# SCH_fpga_v1_2023-12-09.net
KiCad netlist of a schematic drawn in EasyEDA
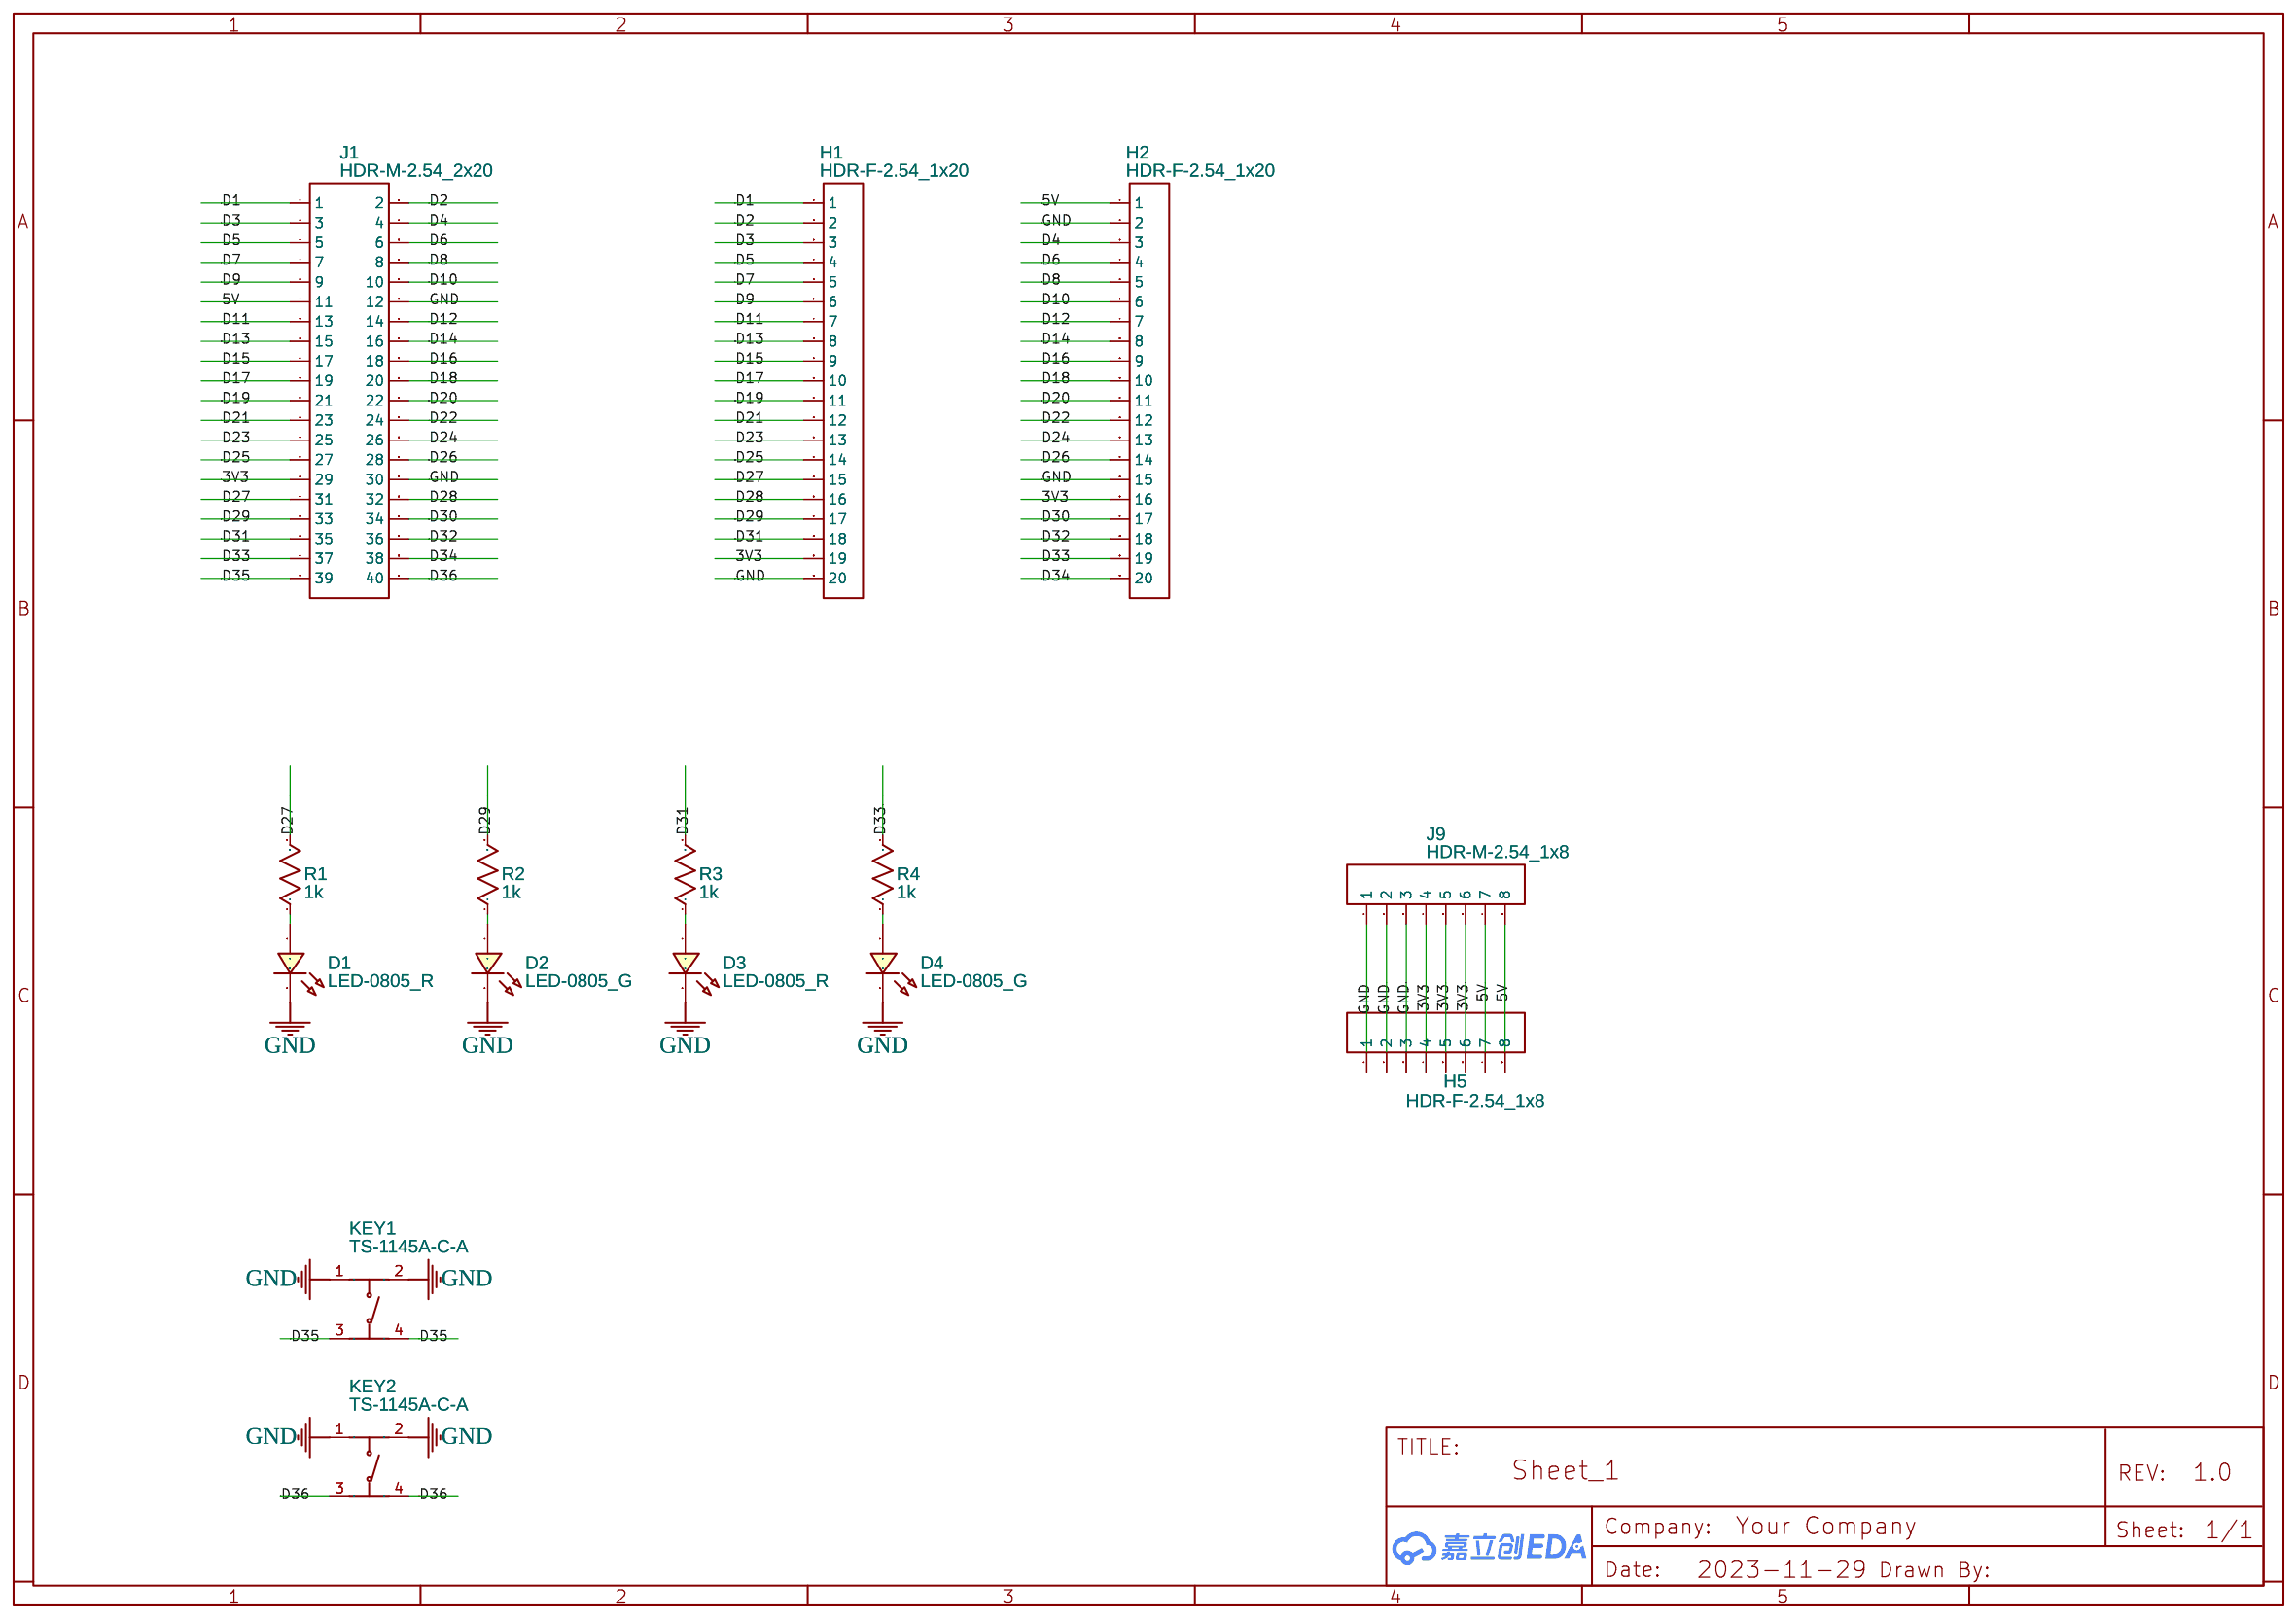
[diagram p0: Sheet_in]
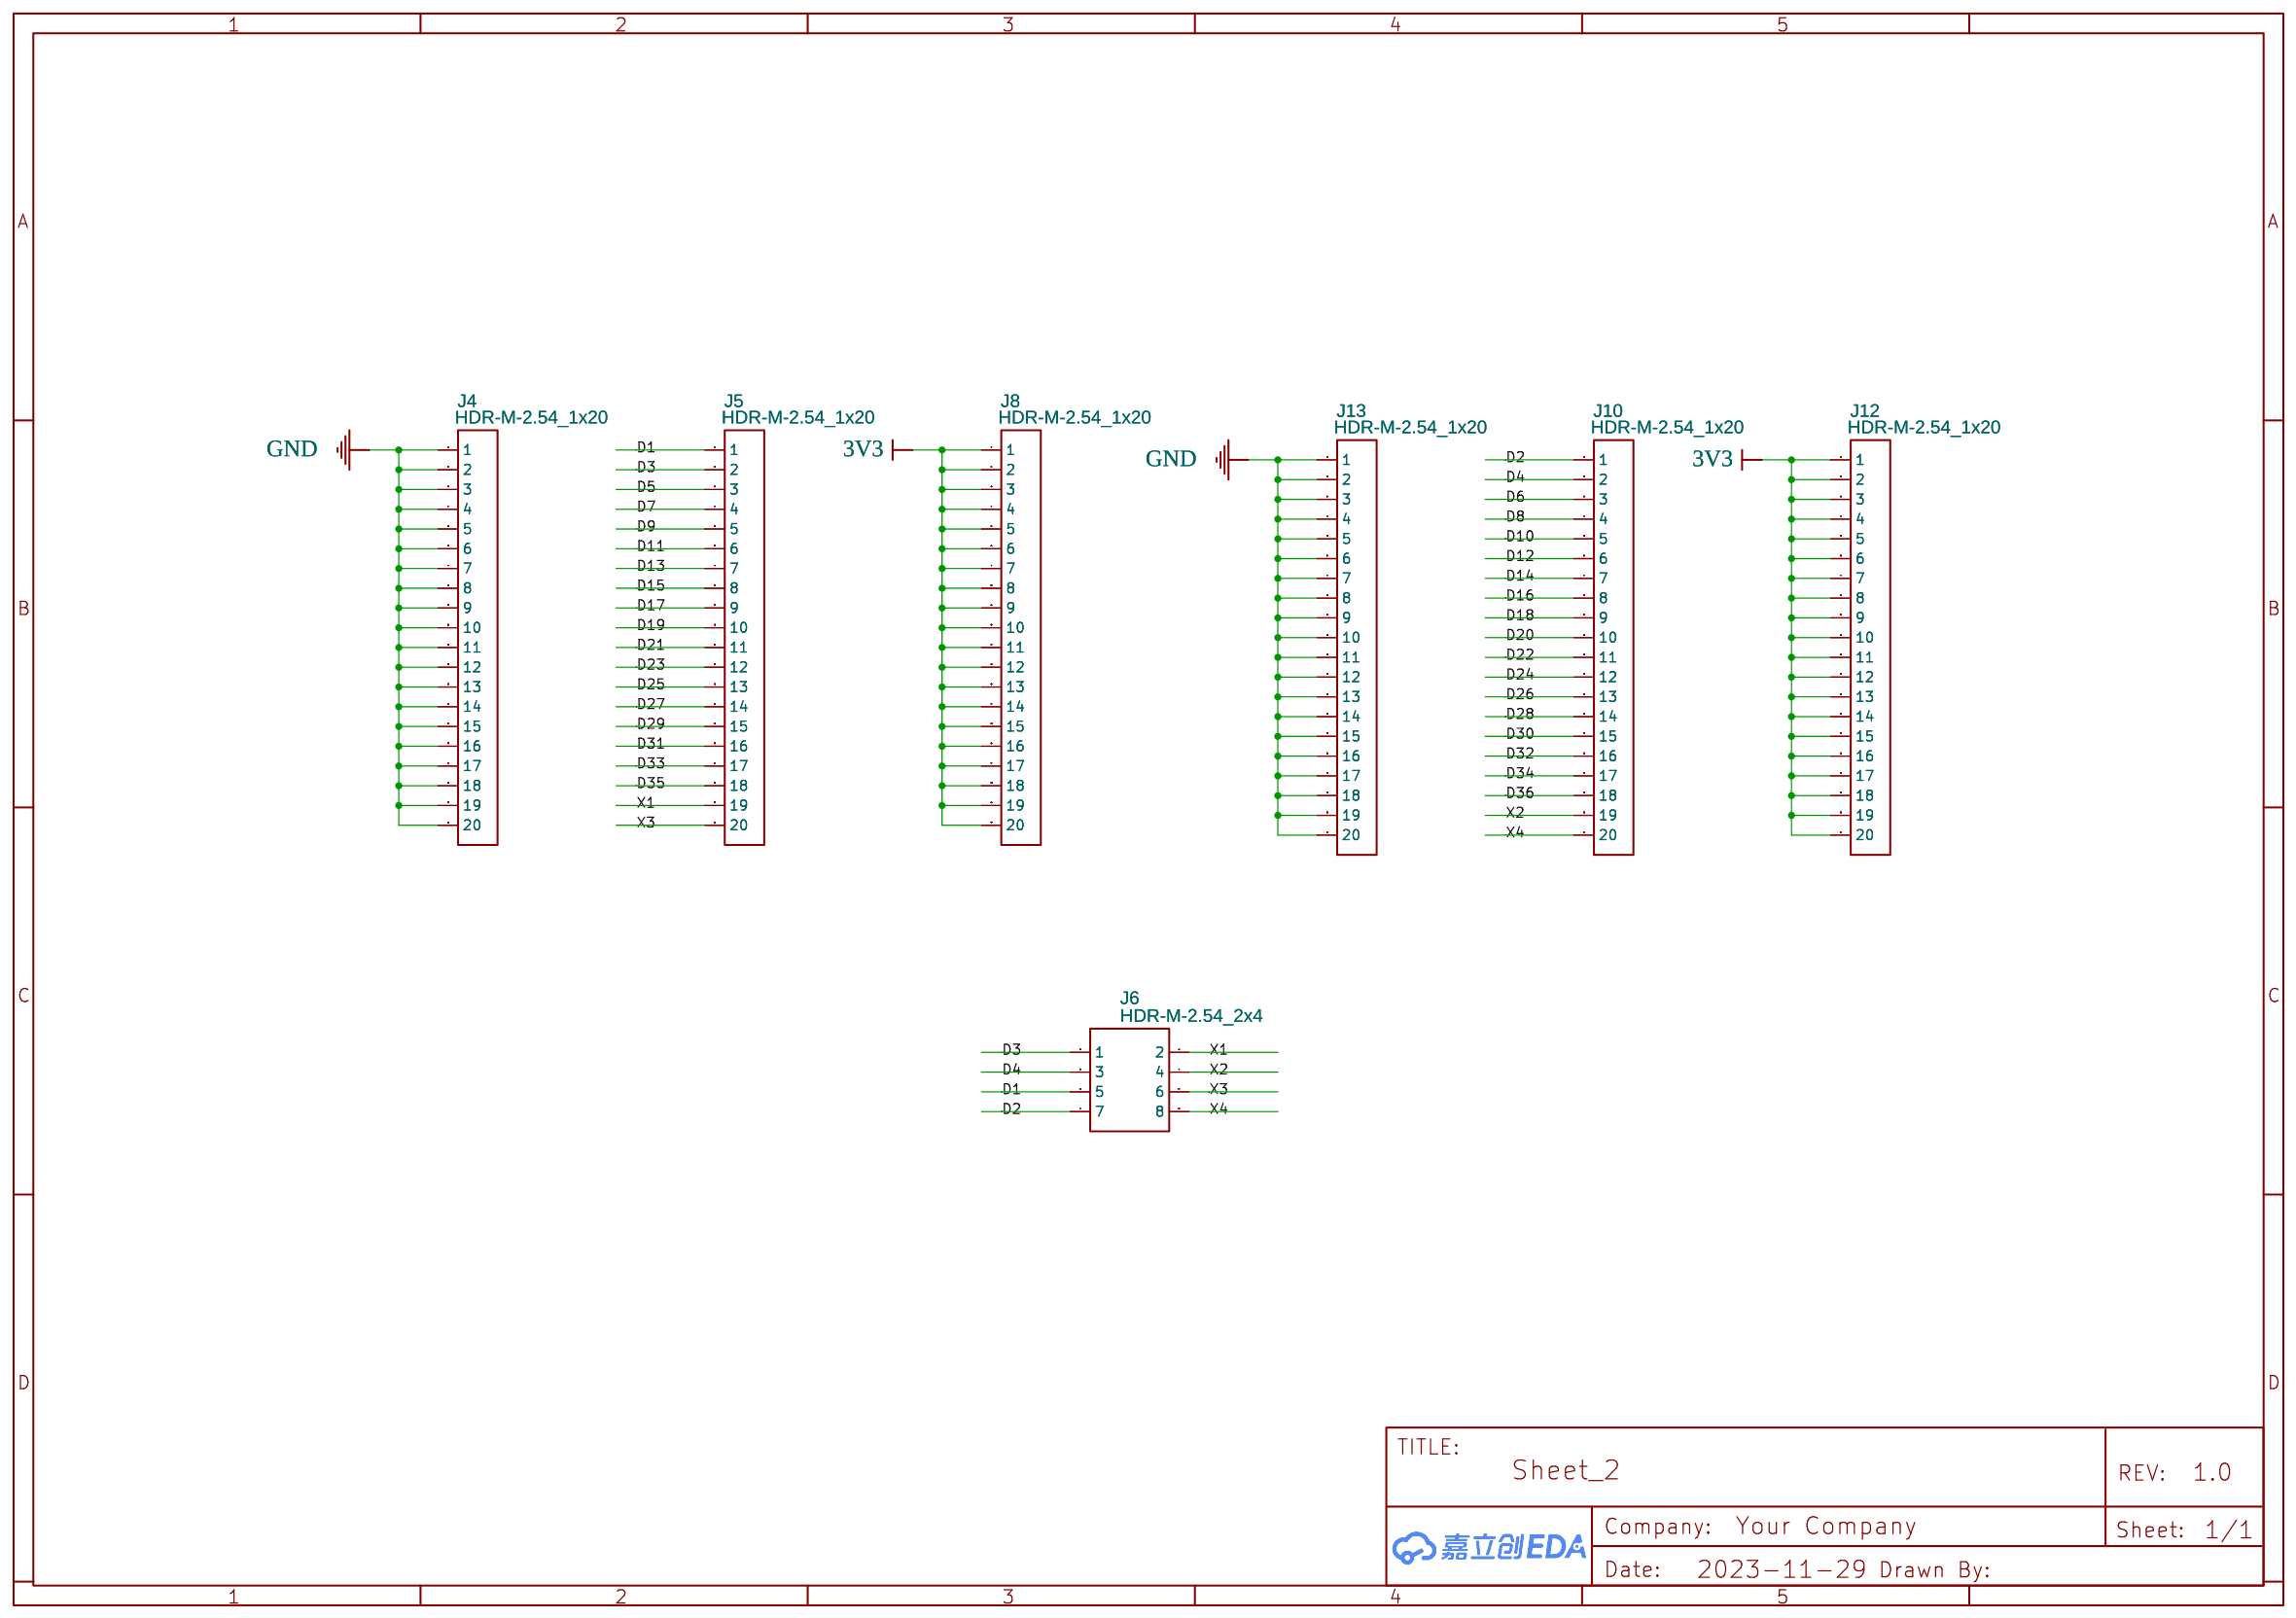
[diagram p1: Sheet_ctrl]
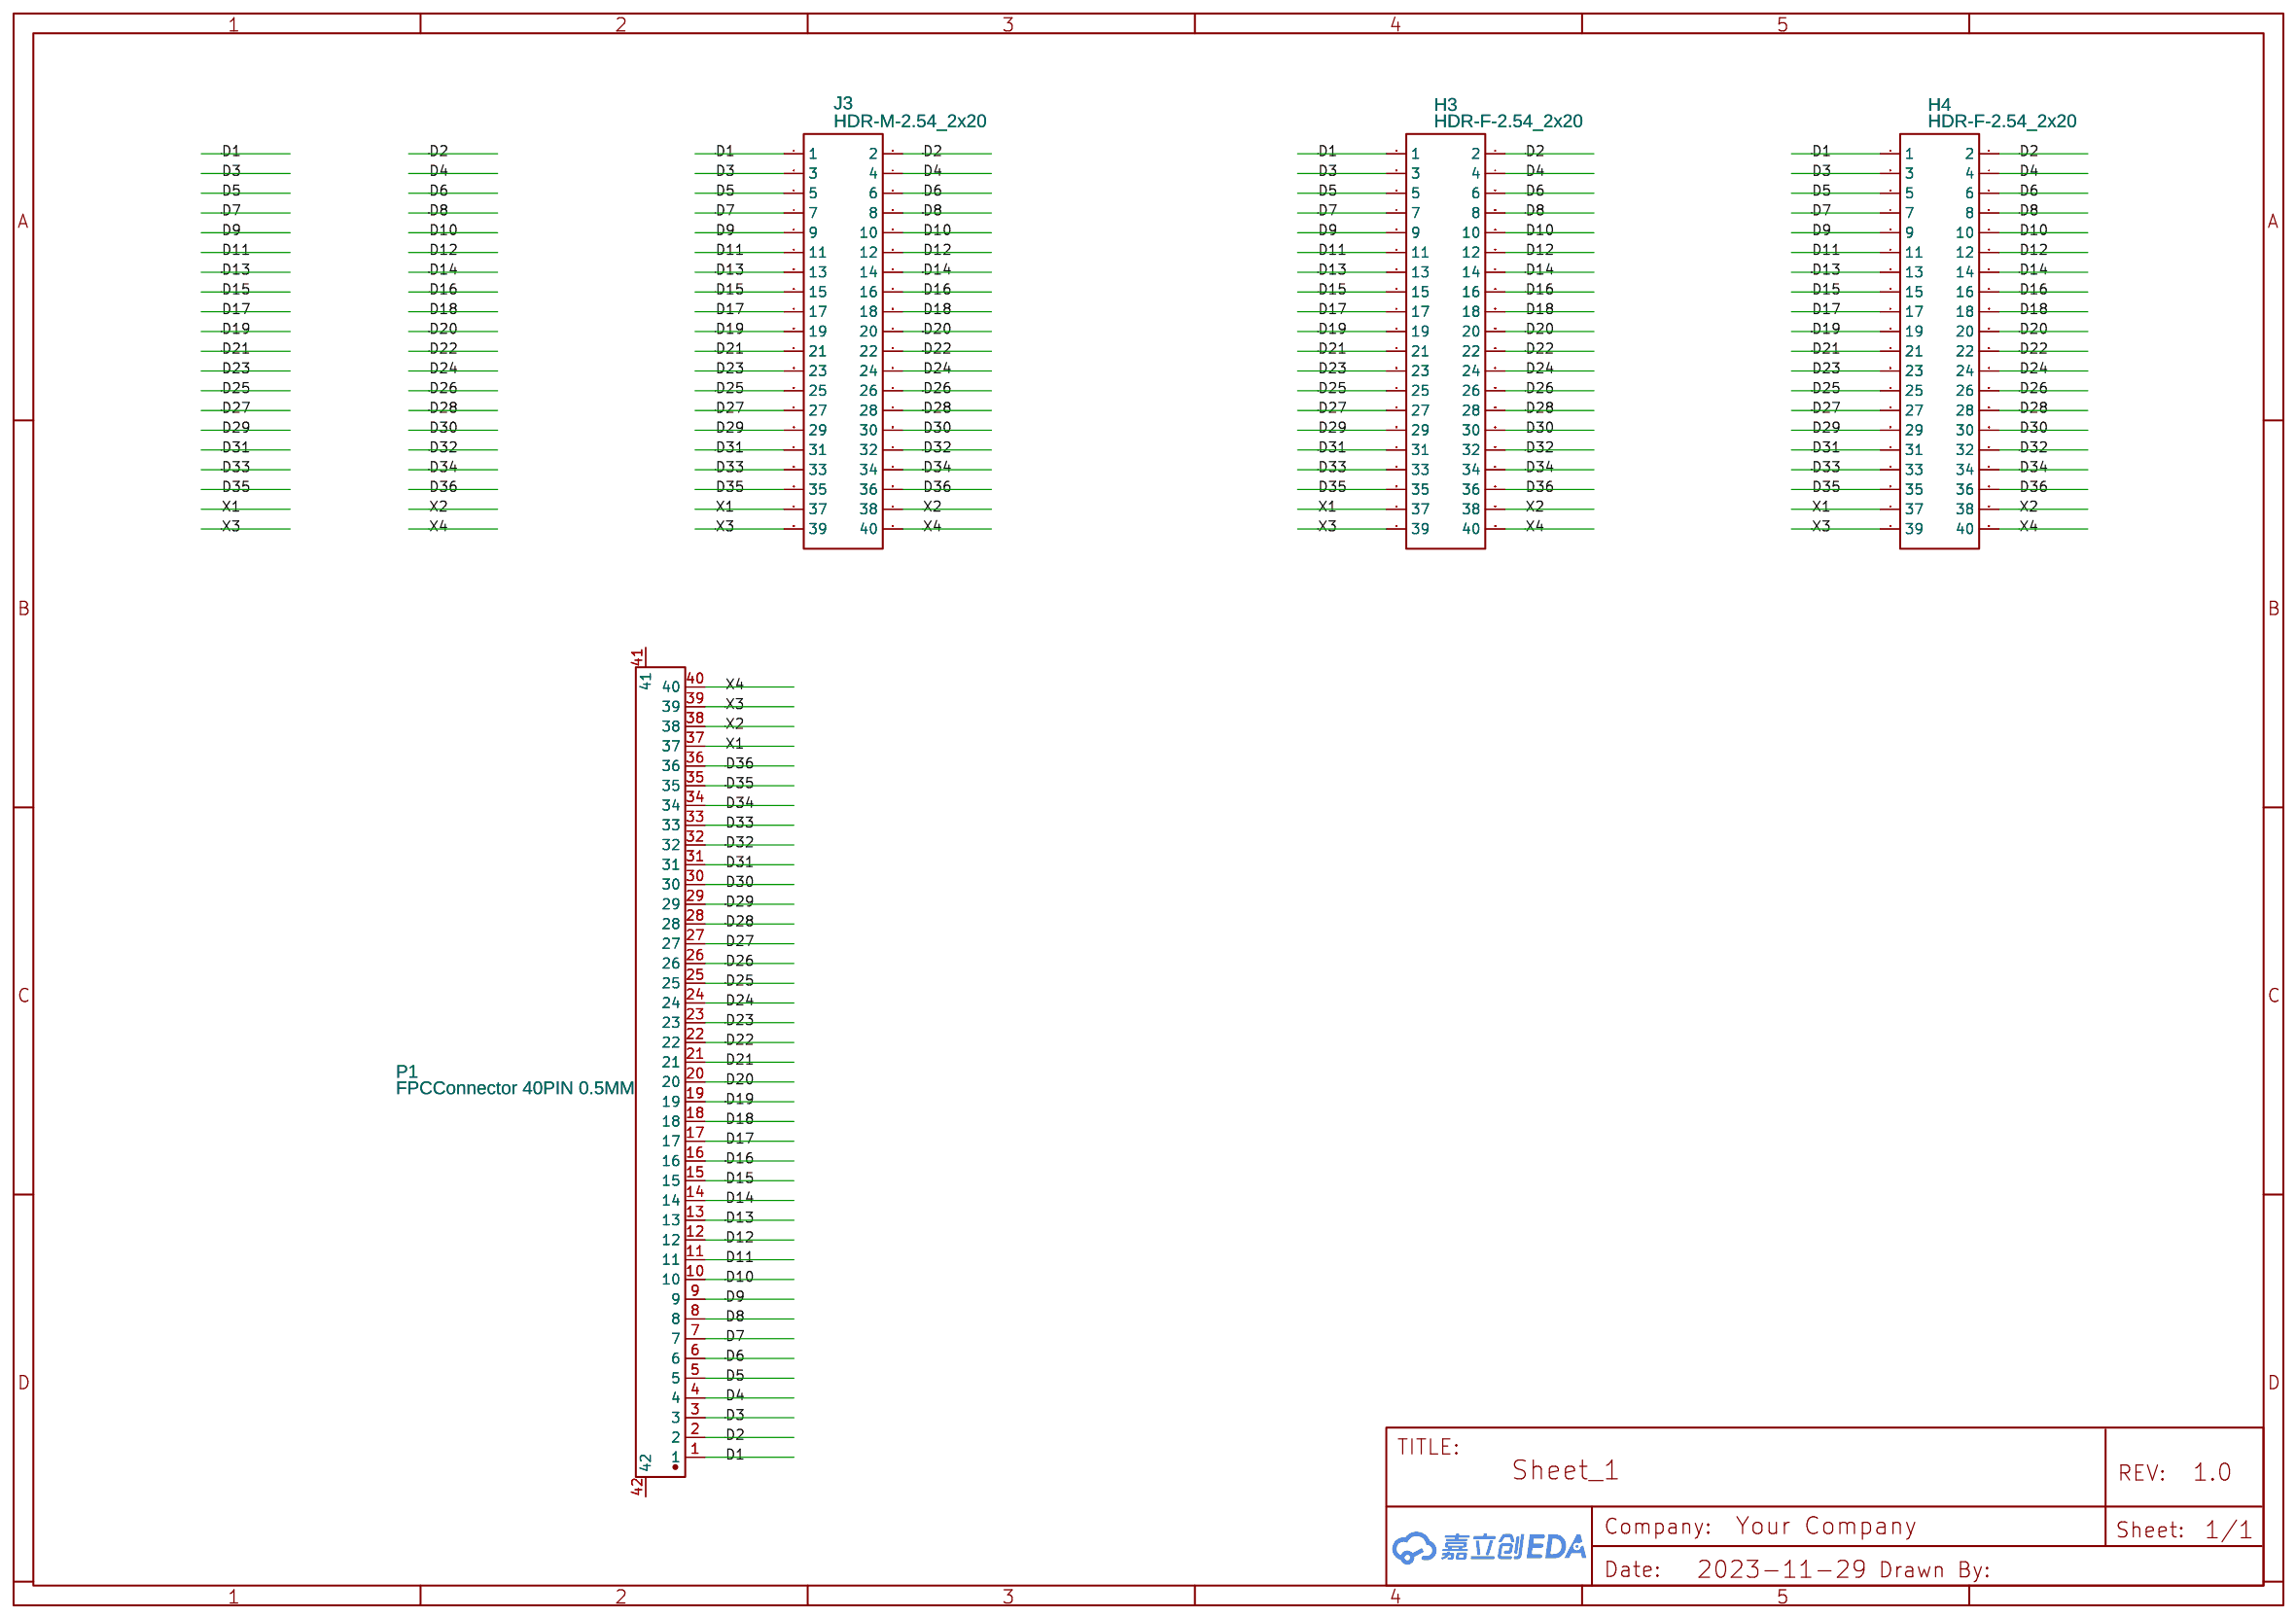
[diagram p2: Sheet_out]

(export (version "E")
  (design (tool "Eeschema 10.0.6"))
  (components
    (comp (ref "D1")
      (value "LED-0805_R")
      (fields
        (field (name "BOM_Manufacturer Part") "17-21SURC/S530-A3/TR8")
        (field (name "BOM_Supplier Part") "C72037")
      )
      (libsource (lib "") (part "LED-0805_R"))
    )
    (comp (ref "D2")
      (value "LED-0805_G")
      (fields (field (name "BOM_Manufacturer Part") "NCD0805G1") (field (name "BOM_Supplier Part") "C84260"))
      (libsource (lib "") (part "LED-0805_G"))
    )
    (comp (ref "D3")
      (value "LED-0805_R")
      (fields
        (field (name "BOM_Manufacturer Part") "17-21SURC/S530-A3/TR8")
        (field (name "BOM_Supplier Part") "C72037")
      )
      (libsource (lib "") (part "LED-0805_R"))
    )
    (comp (ref "D4")
      (value "LED-0805_G")
      (fields (field (name "BOM_Manufacturer Part") "NCD0805G1") (field (name "BOM_Supplier Part") "C84260"))
      (libsource (lib "") (part "LED-0805_G"))
    )
    (comp (ref "H1")
      (value "HDR-F-2.54_1x20")
      (fields (field (name "BOM_Supplier Part") "C50984"))
      (libsource (lib "") (part "HDR-F-2.54_1x20"))
    )
    (comp (ref "H2")
      (value "HDR-F-2.54_1x20")
      (fields (field (name "BOM_Supplier Part") "C50984"))
      (libsource (lib "") (part "HDR-F-2.54_1x20"))
    )
    (comp (ref "H5")
      (value "HDR-F-2.54_1x8")
      (fields (field (name "BOM_Supplier Part") "C225505"))
      (libsource (lib "") (part "HDR-F-2.54_1x8"))
    )
    (comp (ref "J1")
      (value "HDR-M-2.54_2x20")
      (fields (field (name "BOM_Supplier Part") "C50980"))
      (libsource (lib "") (part "HDR-M-2.54_2x20"))
    )
    (comp (ref "J9")
      (value "HDR-M-2.54_1x8")
      (fields (field (name "BOM_Supplier Part") "C190820"))
      (libsource (lib "") (part "HDR-M-2.54_1x8"))
    )
    (comp (ref "KEY1")
      (value "TS-1145A-C-A")
      (fields (field (name "BOM_Supplier Part") "C318903"))
      (libsource (lib "") (part "TS-1145A-C-A"))
    )
    (comp (ref "KEY2")
      (value "TS-1145A-C-A")
      (fields (field (name "BOM_Supplier Part") "C318903"))
      (libsource (lib "") (part "TS-1145A-C-A"))
    )
    (comp (ref "R1")
      (value "1k")
      (fields
        (field (name "BOM_Manufacturer Part") "TC0525F1001T5E")
        (field (name "BOM_Supplier Part") "C75781")
      )
      (libsource (lib "") (part "R_0805_US"))
    )
    (comp (ref "R2")
      (value "1k")
      (fields
        (field (name "BOM_Manufacturer Part") "TC0525F1001T5E")
        (field (name "BOM_Supplier Part") "C75781")
      )
      (libsource (lib "") (part "R_0805_US"))
    )
    (comp (ref "R3")
      (value "1k")
      (fields
        (field (name "BOM_Manufacturer Part") "TC0525F1001T5E")
        (field (name "BOM_Supplier Part") "C75781")
      )
      (libsource (lib "") (part "R_0805_US"))
    )
    (comp (ref "R4")
      (value "1k")
      (fields
        (field (name "BOM_Manufacturer Part") "TC0525F1001T5E")
        (field (name "BOM_Supplier Part") "C75781")
      )
      (libsource (lib "") (part "R_0805_US"))
    )
    (comp (ref "J4")
      (value "HDR-M-2.54_1x20")
      (fields (field (name "BOM_Supplier Part") "C50981"))
      (libsource (lib "") (part "HDR-M-2.54_1x20"))
    )
    (comp (ref "J5")
      (value "HDR-M-2.54_1x20")
      (fields (field (name "BOM_Supplier Part") "C50981"))
      (libsource (lib "") (part "HDR-M-2.54_1x20"))
    )
    (comp (ref "J6")
      (value "HDR-M-2.54_2x4")
      (fields (field (name "BOM_Supplier Part") "C58363"))
      (libsource (lib "") (part "HDR-M-2.54_2x4"))
    )
    (comp (ref "J8")
      (value "HDR-M-2.54_1x20")
      (fields (field (name "BOM_Supplier Part") "C50981"))
      (libsource (lib "") (part "HDR-M-2.54_1x20"))
    )
    (comp (ref "J10")
      (value "HDR-M-2.54_1x20")
      (fields (field (name "BOM_Supplier Part") "C50981"))
      (libsource (lib "") (part "HDR-M-2.54_1x20"))
    )
    (comp (ref "J12")
      (value "HDR-M-2.54_1x20")
      (fields (field (name "BOM_Supplier Part") "C50981"))
      (libsource (lib "") (part "HDR-M-2.54_1x20"))
    )
    (comp (ref "J13")
      (value "HDR-M-2.54_1x20")
      (fields (field (name "BOM_Supplier Part") "C50981"))
      (libsource (lib "") (part "HDR-M-2.54_1x20"))
    )
    (comp (ref "H3")
      (value "HDR-F-2.54_2x20")
      (fields (field (name "BOM_Supplier Part") "C50982"))
      (libsource (lib "") (part "HDR-F-2.54_2x20"))
    )
    (comp (ref "H4")
      (value "HDR-F-2.54_2x20")
      (fields (field (name "BOM_Supplier Part") "C50982"))
      (libsource (lib "") (part "HDR-F-2.54_2x20"))
    )
    (comp (ref "J3")
      (value "HDR-M-2.54_2x20")
      (fields (field (name "BOM_Supplier Part") "C50980"))
      (libsource (lib "") (part "HDR-M-2.54_2x20"))
    )
    (comp (ref "P1")
      (value "FPCConnector 40PIN 0.5MM")
      (fields (field (name "BOM_Manufacturer Part") "0.5-40P翻盖") (field (name "BOM_Supplier Part") "C9160"))
      (libsource (lib "") (part "FPCConnector 40PIN 0.5MM"))
    )
  )
  (nets
    (net (code "1") (name "3V3") (class "Default")
      (node (ref "H1") (pin "19") (pinfunction "19_19") (pintype "unspecified"))
      (node (ref "H2") (pin "16") (pinfunction "16_16") (pintype "unspecified"))
      (node (ref "H5") (pin "4") (pinfunction "4_4") (pintype "unspecified"))
      (node (ref "H5") (pin "5") (pinfunction "5_5") (pintype "unspecified"))
      (node (ref "H5") (pin "6") (pinfunction "6_6") (pintype "unspecified"))
      (node (ref "J1") (pin "29") (pinfunction "29_29") (pintype "input"))
      (node (ref "J12") (pin "1") (pinfunction "1_1") (pintype "unspecified"))
      (node (ref "J12") (pin "10") (pinfunction "10_10") (pintype "unspecified"))
      (node (ref "J12") (pin "11") (pinfunction "11_11") (pintype "unspecified"))
      (node (ref "J12") (pin "12") (pinfunction "12_12") (pintype "unspecified"))
      (node (ref "J12") (pin "13") (pinfunction "13_13") (pintype "unspecified"))
      (node (ref "J12") (pin "14") (pinfunction "14_14") (pintype "unspecified"))
      (node (ref "J12") (pin "15") (pinfunction "15_15") (pintype "unspecified"))
      (node (ref "J12") (pin "16") (pinfunction "16_16") (pintype "unspecified"))
      (node (ref "J12") (pin "17") (pinfunction "17_17") (pintype "unspecified"))
      (node (ref "J12") (pin "18") (pinfunction "18_18") (pintype "unspecified"))
      (node (ref "J12") (pin "19") (pinfunction "19_19") (pintype "unspecified"))
      (node (ref "J12") (pin "2") (pinfunction "2_2") (pintype "unspecified"))
      (node (ref "J12") (pin "20") (pinfunction "20_20") (pintype "unspecified"))
      (node (ref "J12") (pin "3") (pinfunction "3_3") (pintype "unspecified"))
      (node (ref "J12") (pin "4") (pinfunction "4_4") (pintype "unspecified"))
      (node (ref "J12") (pin "5") (pinfunction "5_5") (pintype "unspecified"))
      (node (ref "J12") (pin "6") (pinfunction "6_6") (pintype "unspecified"))
      (node (ref "J12") (pin "7") (pinfunction "7_7") (pintype "unspecified"))
      (node (ref "J12") (pin "8") (pinfunction "8_8") (pintype "unspecified"))
      (node (ref "J12") (pin "9") (pinfunction "9_9") (pintype "unspecified"))
      (node (ref "J8") (pin "1") (pinfunction "1_1") (pintype "unspecified"))
      (node (ref "J8") (pin "10") (pinfunction "10_10") (pintype "unspecified"))
      (node (ref "J8") (pin "11") (pinfunction "11_11") (pintype "unspecified"))
      (node (ref "J8") (pin "12") (pinfunction "12_12") (pintype "unspecified"))
      (node (ref "J8") (pin "13") (pinfunction "13_13") (pintype "unspecified"))
      (node (ref "J8") (pin "14") (pinfunction "14_14") (pintype "unspecified"))
      (node (ref "J8") (pin "15") (pinfunction "15_15") (pintype "unspecified"))
      (node (ref "J8") (pin "16") (pinfunction "16_16") (pintype "unspecified"))
      (node (ref "J8") (pin "17") (pinfunction "17_17") (pintype "unspecified"))
      (node (ref "J8") (pin "18") (pinfunction "18_18") (pintype "unspecified"))
      (node (ref "J8") (pin "19") (pinfunction "19_19") (pintype "unspecified"))
      (node (ref "J8") (pin "2") (pinfunction "2_2") (pintype "unspecified"))
      (node (ref "J8") (pin "20") (pinfunction "20_20") (pintype "unspecified"))
      (node (ref "J8") (pin "3") (pinfunction "3_3") (pintype "unspecified"))
      (node (ref "J8") (pin "4") (pinfunction "4_4") (pintype "unspecified"))
      (node (ref "J8") (pin "5") (pinfunction "5_5") (pintype "unspecified"))
      (node (ref "J8") (pin "6") (pinfunction "6_6") (pintype "unspecified"))
      (node (ref "J8") (pin "7") (pinfunction "7_7") (pintype "unspecified"))
      (node (ref "J8") (pin "8") (pinfunction "8_8") (pintype "unspecified"))
      (node (ref "J8") (pin "9") (pinfunction "9_9") (pintype "unspecified"))
      (node (ref "J9") (pin "4") (pinfunction "4_4") (pintype "unspecified"))
      (node (ref "J9") (pin "5") (pinfunction "5_5") (pintype "unspecified"))
      (node (ref "J9") (pin "6") (pinfunction "6_6") (pintype "unspecified"))
    )
    (net (code "2") (name "5V") (class "Default")
      (node (ref "H2") (pin "1") (pinfunction "1_1") (pintype "unspecified"))
      (node (ref "H5") (pin "7") (pinfunction "7_7") (pintype "unspecified"))
      (node (ref "H5") (pin "8") (pinfunction "8_8") (pintype "unspecified"))
      (node (ref "J1") (pin "11") (pinfunction "11_11") (pintype "input"))
      (node (ref "J9") (pin "7") (pinfunction "7_7") (pintype "unspecified"))
      (node (ref "J9") (pin "8") (pinfunction "8_8") (pintype "unspecified"))
    )
    (net (code "3") (name "D1") (class "Default")
      (node (ref "H1") (pin "1") (pinfunction "1_1") (pintype "unspecified"))
      (node (ref "H3") (pin "1") (pinfunction "1_1") (pintype "input"))
      (node (ref "H4") (pin "1") (pinfunction "1_1") (pintype "input"))
      (node (ref "J1") (pin "1") (pinfunction "1_1") (pintype "input"))
      (node (ref "J3") (pin "1") (pinfunction "1_1") (pintype "input"))
      (node (ref "J5") (pin "1") (pinfunction "1_1") (pintype "unspecified"))
      (node (ref "J6") (pin "5") (pinfunction "5_5") (pintype "unspecified"))
      (node (ref "P1") (pin "1") (pinfunction "1_1") (pintype "unspecified"))
    )
    (net (code "4") (name "D2") (class "Default")
      (node (ref "H1") (pin "2") (pinfunction "2_2") (pintype "unspecified"))
      (node (ref "H3") (pin "2") (pinfunction "2_2") (pintype "input"))
      (node (ref "H4") (pin "2") (pinfunction "2_2") (pintype "input"))
      (node (ref "J1") (pin "2") (pinfunction "2_2") (pintype "input"))
      (node (ref "J10") (pin "1") (pinfunction "1_1") (pintype "unspecified"))
      (node (ref "J3") (pin "2") (pinfunction "2_2") (pintype "input"))
      (node (ref "J6") (pin "7") (pinfunction "7_7") (pintype "unspecified"))
      (node (ref "P1") (pin "2") (pinfunction "2_2") (pintype "unspecified"))
    )
    (net (code "5") (name "D3") (class "Default")
      (node (ref "H1") (pin "3") (pinfunction "3_3") (pintype "unspecified"))
      (node (ref "H3") (pin "3") (pinfunction "3_3") (pintype "input"))
      (node (ref "H4") (pin "3") (pinfunction "3_3") (pintype "input"))
      (node (ref "J1") (pin "3") (pinfunction "3_3") (pintype "input"))
      (node (ref "J3") (pin "3") (pinfunction "3_3") (pintype "input"))
      (node (ref "J5") (pin "2") (pinfunction "2_2") (pintype "unspecified"))
      (node (ref "J6") (pin "1") (pinfunction "1_1") (pintype "unspecified"))
      (node (ref "P1") (pin "3") (pinfunction "3_3") (pintype "unspecified"))
    )
    (net (code "6") (name "D4") (class "Default")
      (node (ref "H2") (pin "3") (pinfunction "3_3") (pintype "unspecified"))
      (node (ref "H3") (pin "4") (pinfunction "4_4") (pintype "input"))
      (node (ref "H4") (pin "4") (pinfunction "4_4") (pintype "input"))
      (node (ref "J1") (pin "4") (pinfunction "4_4") (pintype "input"))
      (node (ref "J10") (pin "2") (pinfunction "2_2") (pintype "unspecified"))
      (node (ref "J3") (pin "4") (pinfunction "4_4") (pintype "input"))
      (node (ref "J6") (pin "3") (pinfunction "3_3") (pintype "unspecified"))
      (node (ref "P1") (pin "4") (pinfunction "4_4") (pintype "unspecified"))
    )
    (net (code "7") (name "D5") (class "Default")
      (node (ref "H1") (pin "4") (pinfunction "4_4") (pintype "unspecified"))
      (node (ref "H3") (pin "5") (pinfunction "5_5") (pintype "input"))
      (node (ref "H4") (pin "5") (pinfunction "5_5") (pintype "input"))
      (node (ref "J1") (pin "5") (pinfunction "5_5") (pintype "input"))
      (node (ref "J3") (pin "5") (pinfunction "5_5") (pintype "input"))
      (node (ref "J5") (pin "3") (pinfunction "3_3") (pintype "unspecified"))
      (node (ref "P1") (pin "5") (pinfunction "5_5") (pintype "unspecified"))
    )
    (net (code "8") (name "D6") (class "Default")
      (node (ref "H2") (pin "4") (pinfunction "4_4") (pintype "unspecified"))
      (node (ref "H3") (pin "6") (pinfunction "6_6") (pintype "input"))
      (node (ref "H4") (pin "6") (pinfunction "6_6") (pintype "input"))
      (node (ref "J1") (pin "6") (pinfunction "6_6") (pintype "input"))
      (node (ref "J10") (pin "3") (pinfunction "3_3") (pintype "unspecified"))
      (node (ref "J3") (pin "6") (pinfunction "6_6") (pintype "input"))
      (node (ref "P1") (pin "6") (pinfunction "6_6") (pintype "unspecified"))
    )
    (net (code "9") (name "D7") (class "Default")
      (node (ref "H1") (pin "5") (pinfunction "5_5") (pintype "unspecified"))
      (node (ref "H3") (pin "7") (pinfunction "7_7") (pintype "input"))
      (node (ref "H4") (pin "7") (pinfunction "7_7") (pintype "input"))
      (node (ref "J1") (pin "7") (pinfunction "7_7") (pintype "input"))
      (node (ref "J3") (pin "7") (pinfunction "7_7") (pintype "input"))
      (node (ref "J5") (pin "4") (pinfunction "4_4") (pintype "unspecified"))
      (node (ref "P1") (pin "7") (pinfunction "7_7") (pintype "unspecified"))
    )
    (net (code "10") (name "D8") (class "Default")
      (node (ref "H2") (pin "5") (pinfunction "5_5") (pintype "unspecified"))
      (node (ref "H3") (pin "8") (pinfunction "8_8") (pintype "input"))
      (node (ref "H4") (pin "8") (pinfunction "8_8") (pintype "input"))
      (node (ref "J1") (pin "8") (pinfunction "8_8") (pintype "input"))
      (node (ref "J10") (pin "4") (pinfunction "4_4") (pintype "unspecified"))
      (node (ref "J3") (pin "8") (pinfunction "8_8") (pintype "input"))
      (node (ref "P1") (pin "8") (pinfunction "8_8") (pintype "unspecified"))
    )
    (net (code "11") (name "D9") (class "Default")
      (node (ref "H1") (pin "6") (pinfunction "6_6") (pintype "unspecified"))
      (node (ref "H3") (pin "9") (pinfunction "9_9") (pintype "input"))
      (node (ref "H4") (pin "9") (pinfunction "9_9") (pintype "input"))
      (node (ref "J1") (pin "9") (pinfunction "9_9") (pintype "input"))
      (node (ref "J3") (pin "9") (pinfunction "9_9") (pintype "input"))
      (node (ref "J5") (pin "5") (pinfunction "5_5") (pintype "unspecified"))
      (node (ref "P1") (pin "9") (pinfunction "9_9") (pintype "unspecified"))
    )
    (net (code "12") (name "D10") (class "Default")
      (node (ref "H2") (pin "6") (pinfunction "6_6") (pintype "unspecified"))
      (node (ref "H3") (pin "10") (pinfunction "10_10") (pintype "input"))
      (node (ref "H4") (pin "10") (pinfunction "10_10") (pintype "input"))
      (node (ref "J1") (pin "10") (pinfunction "10_10") (pintype "input"))
      (node (ref "J10") (pin "5") (pinfunction "5_5") (pintype "unspecified"))
      (node (ref "J3") (pin "10") (pinfunction "10_10") (pintype "input"))
      (node (ref "P1") (pin "10") (pinfunction "10_10") (pintype "unspecified"))
    )
    (net (code "13") (name "D11") (class "Default")
      (node (ref "H1") (pin "7") (pinfunction "7_7") (pintype "unspecified"))
      (node (ref "H3") (pin "11") (pinfunction "11_11") (pintype "input"))
      (node (ref "H4") (pin "11") (pinfunction "11_11") (pintype "input"))
      (node (ref "J1") (pin "13") (pinfunction "13_13") (pintype "input"))
      (node (ref "J3") (pin "11") (pinfunction "11_11") (pintype "input"))
      (node (ref "J5") (pin "6") (pinfunction "6_6") (pintype "unspecified"))
      (node (ref "P1") (pin "11") (pinfunction "11_11") (pintype "unspecified"))
    )
    (net (code "14") (name "D12") (class "Default")
      (node (ref "H2") (pin "7") (pinfunction "7_7") (pintype "unspecified"))
      (node (ref "H3") (pin "12") (pinfunction "12_12") (pintype "input"))
      (node (ref "H4") (pin "12") (pinfunction "12_12") (pintype "input"))
      (node (ref "J1") (pin "14") (pinfunction "14_14") (pintype "input"))
      (node (ref "J10") (pin "6") (pinfunction "6_6") (pintype "unspecified"))
      (node (ref "J3") (pin "12") (pinfunction "12_12") (pintype "input"))
      (node (ref "P1") (pin "12") (pinfunction "12_12") (pintype "unspecified"))
    )
    (net (code "15") (name "D13") (class "Default")
      (node (ref "H1") (pin "8") (pinfunction "8_8") (pintype "unspecified"))
      (node (ref "H3") (pin "13") (pinfunction "13_13") (pintype "input"))
      (node (ref "H4") (pin "13") (pinfunction "13_13") (pintype "input"))
      (node (ref "J1") (pin "15") (pinfunction "15_15") (pintype "input"))
      (node (ref "J3") (pin "13") (pinfunction "13_13") (pintype "input"))
      (node (ref "J5") (pin "7") (pinfunction "7_7") (pintype "unspecified"))
      (node (ref "P1") (pin "13") (pinfunction "13_13") (pintype "unspecified"))
    )
    (net (code "16") (name "D14") (class "Default")
      (node (ref "H2") (pin "8") (pinfunction "8_8") (pintype "unspecified"))
      (node (ref "H3") (pin "14") (pinfunction "14_14") (pintype "input"))
      (node (ref "H4") (pin "14") (pinfunction "14_14") (pintype "input"))
      (node (ref "J1") (pin "16") (pinfunction "16_16") (pintype "input"))
      (node (ref "J10") (pin "7") (pinfunction "7_7") (pintype "unspecified"))
      (node (ref "J3") (pin "14") (pinfunction "14_14") (pintype "input"))
      (node (ref "P1") (pin "14") (pinfunction "14_14") (pintype "unspecified"))
    )
    (net (code "17") (name "D15") (class "Default")
      (node (ref "H1") (pin "9") (pinfunction "9_9") (pintype "unspecified"))
      (node (ref "H3") (pin "15") (pinfunction "15_15") (pintype "input"))
      (node (ref "H4") (pin "15") (pinfunction "15_15") (pintype "input"))
      (node (ref "J1") (pin "17") (pinfunction "17_17") (pintype "input"))
      (node (ref "J3") (pin "15") (pinfunction "15_15") (pintype "input"))
      (node (ref "J5") (pin "8") (pinfunction "8_8") (pintype "unspecified"))
      (node (ref "P1") (pin "15") (pinfunction "15_15") (pintype "unspecified"))
    )
    (net (code "18") (name "D16") (class "Default")
      (node (ref "H2") (pin "9") (pinfunction "9_9") (pintype "unspecified"))
      (node (ref "H3") (pin "16") (pinfunction "16_16") (pintype "input"))
      (node (ref "H4") (pin "16") (pinfunction "16_16") (pintype "input"))
      (node (ref "J1") (pin "18") (pinfunction "18_18") (pintype "input"))
      (node (ref "J10") (pin "8") (pinfunction "8_8") (pintype "unspecified"))
      (node (ref "J3") (pin "16") (pinfunction "16_16") (pintype "input"))
      (node (ref "P1") (pin "16") (pinfunction "16_16") (pintype "unspecified"))
    )
    (net (code "19") (name "D17") (class "Default")
      (node (ref "H1") (pin "10") (pinfunction "10_10") (pintype "unspecified"))
      (node (ref "H3") (pin "17") (pinfunction "17_17") (pintype "input"))
      (node (ref "H4") (pin "17") (pinfunction "17_17") (pintype "input"))
      (node (ref "J1") (pin "19") (pinfunction "19_19") (pintype "input"))
      (node (ref "J3") (pin "17") (pinfunction "17_17") (pintype "input"))
      (node (ref "J5") (pin "9") (pinfunction "9_9") (pintype "unspecified"))
      (node (ref "P1") (pin "17") (pinfunction "17_17") (pintype "unspecified"))
    )
    (net (code "20") (name "D18") (class "Default")
      (node (ref "H2") (pin "10") (pinfunction "10_10") (pintype "unspecified"))
      (node (ref "H3") (pin "18") (pinfunction "18_18") (pintype "input"))
      (node (ref "H4") (pin "18") (pinfunction "18_18") (pintype "input"))
      (node (ref "J1") (pin "20") (pinfunction "20_20") (pintype "input"))
      (node (ref "J10") (pin "9") (pinfunction "9_9") (pintype "unspecified"))
      (node (ref "J3") (pin "18") (pinfunction "18_18") (pintype "input"))
      (node (ref "P1") (pin "18") (pinfunction "18_18") (pintype "unspecified"))
    )
    (net (code "21") (name "D19") (class "Default")
      (node (ref "H1") (pin "11") (pinfunction "11_11") (pintype "unspecified"))
      (node (ref "H3") (pin "19") (pinfunction "19_19") (pintype "input"))
      (node (ref "H4") (pin "19") (pinfunction "19_19") (pintype "input"))
      (node (ref "J1") (pin "21") (pinfunction "21_21") (pintype "input"))
      (node (ref "J3") (pin "19") (pinfunction "19_19") (pintype "input"))
      (node (ref "J5") (pin "10") (pinfunction "10_10") (pintype "unspecified"))
      (node (ref "P1") (pin "19") (pinfunction "19_19") (pintype "unspecified"))
    )
    (net (code "22") (name "D20") (class "Default")
      (node (ref "H2") (pin "11") (pinfunction "11_11") (pintype "unspecified"))
      (node (ref "H3") (pin "20") (pinfunction "20_20") (pintype "input"))
      (node (ref "H4") (pin "20") (pinfunction "20_20") (pintype "input"))
      (node (ref "J1") (pin "22") (pinfunction "22_22") (pintype "input"))
      (node (ref "J10") (pin "10") (pinfunction "10_10") (pintype "unspecified"))
      (node (ref "J3") (pin "20") (pinfunction "20_20") (pintype "input"))
      (node (ref "P1") (pin "20") (pinfunction "20_20") (pintype "unspecified"))
    )
    (net (code "23") (name "D21") (class "Default")
      (node (ref "H1") (pin "12") (pinfunction "12_12") (pintype "unspecified"))
      (node (ref "H3") (pin "21") (pinfunction "21_21") (pintype "input"))
      (node (ref "H4") (pin "21") (pinfunction "21_21") (pintype "input"))
      (node (ref "J1") (pin "23") (pinfunction "23_23") (pintype "input"))
      (node (ref "J3") (pin "21") (pinfunction "21_21") (pintype "input"))
      (node (ref "J5") (pin "11") (pinfunction "11_11") (pintype "unspecified"))
      (node (ref "P1") (pin "21") (pinfunction "21_21") (pintype "unspecified"))
    )
    (net (code "24") (name "D22") (class "Default")
      (node (ref "H2") (pin "12") (pinfunction "12_12") (pintype "unspecified"))
      (node (ref "H3") (pin "22") (pinfunction "22_22") (pintype "input"))
      (node (ref "H4") (pin "22") (pinfunction "22_22") (pintype "input"))
      (node (ref "J1") (pin "24") (pinfunction "24_24") (pintype "input"))
      (node (ref "J10") (pin "11") (pinfunction "11_11") (pintype "unspecified"))
      (node (ref "J3") (pin "22") (pinfunction "22_22") (pintype "input"))
      (node (ref "P1") (pin "22") (pinfunction "22_22") (pintype "unspecified"))
    )
    (net (code "25") (name "D23") (class "Default")
      (node (ref "H1") (pin "13") (pinfunction "13_13") (pintype "unspecified"))
      (node (ref "H3") (pin "23") (pinfunction "23_23") (pintype "input"))
      (node (ref "H4") (pin "23") (pinfunction "23_23") (pintype "input"))
      (node (ref "J1") (pin "25") (pinfunction "25_25") (pintype "input"))
      (node (ref "J3") (pin "23") (pinfunction "23_23") (pintype "input"))
      (node (ref "J5") (pin "12") (pinfunction "12_12") (pintype "unspecified"))
      (node (ref "P1") (pin "23") (pinfunction "23_23") (pintype "unspecified"))
    )
    (net (code "26") (name "D24") (class "Default")
      (node (ref "H2") (pin "13") (pinfunction "13_13") (pintype "unspecified"))
      (node (ref "H3") (pin "24") (pinfunction "24_24") (pintype "input"))
      (node (ref "H4") (pin "24") (pinfunction "24_24") (pintype "input"))
      (node (ref "J1") (pin "26") (pinfunction "26_26") (pintype "input"))
      (node (ref "J10") (pin "12") (pinfunction "12_12") (pintype "unspecified"))
      (node (ref "J3") (pin "24") (pinfunction "24_24") (pintype "input"))
      (node (ref "P1") (pin "24") (pinfunction "24_24") (pintype "unspecified"))
    )
    (net (code "27") (name "D25") (class "Default")
      (node (ref "H1") (pin "14") (pinfunction "14_14") (pintype "unspecified"))
      (node (ref "H3") (pin "25") (pinfunction "25_25") (pintype "input"))
      (node (ref "H4") (pin "25") (pinfunction "25_25") (pintype "input"))
      (node (ref "J1") (pin "27") (pinfunction "27_27") (pintype "input"))
      (node (ref "J3") (pin "25") (pinfunction "25_25") (pintype "input"))
      (node (ref "J5") (pin "13") (pinfunction "13_13") (pintype "unspecified"))
      (node (ref "P1") (pin "25") (pinfunction "25_25") (pintype "unspecified"))
    )
    (net (code "28") (name "D26") (class "Default")
      (node (ref "H2") (pin "14") (pinfunction "14_14") (pintype "unspecified"))
      (node (ref "H3") (pin "26") (pinfunction "26_26") (pintype "input"))
      (node (ref "H4") (pin "26") (pinfunction "26_26") (pintype "input"))
      (node (ref "J1") (pin "28") (pinfunction "28_28") (pintype "input"))
      (node (ref "J10") (pin "13") (pinfunction "13_13") (pintype "unspecified"))
      (node (ref "J3") (pin "26") (pinfunction "26_26") (pintype "input"))
      (node (ref "P1") (pin "26") (pinfunction "26_26") (pintype "unspecified"))
    )
    (net (code "29") (name "D27") (class "Default")
      (node (ref "H1") (pin "15") (pinfunction "15_15") (pintype "unspecified"))
      (node (ref "H3") (pin "27") (pinfunction "27_27") (pintype "input"))
      (node (ref "H4") (pin "27") (pinfunction "27_27") (pintype "input"))
      (node (ref "J1") (pin "31") (pinfunction "31_31") (pintype "input"))
      (node (ref "J3") (pin "27") (pinfunction "27_27") (pintype "input"))
      (node (ref "J5") (pin "14") (pinfunction "14_14") (pintype "unspecified"))
      (node (ref "P1") (pin "27") (pinfunction "27_27") (pintype "unspecified"))
      (node (ref "R1") (pin "2") (pinfunction "2_2") (pintype "unspecified"))
    )
    (net (code "30") (name "D28") (class "Default")
      (node (ref "H1") (pin "16") (pinfunction "16_16") (pintype "unspecified"))
      (node (ref "H3") (pin "28") (pinfunction "28_28") (pintype "input"))
      (node (ref "H4") (pin "28") (pinfunction "28_28") (pintype "input"))
      (node (ref "J1") (pin "32") (pinfunction "32_32") (pintype "input"))
      (node (ref "J10") (pin "14") (pinfunction "14_14") (pintype "unspecified"))
      (node (ref "J3") (pin "28") (pinfunction "28_28") (pintype "input"))
      (node (ref "P1") (pin "28") (pinfunction "28_28") (pintype "unspecified"))
    )
    (net (code "31") (name "D29") (class "Default")
      (node (ref "H1") (pin "17") (pinfunction "17_17") (pintype "unspecified"))
      (node (ref "H3") (pin "29") (pinfunction "29_29") (pintype "input"))
      (node (ref "H4") (pin "29") (pinfunction "29_29") (pintype "input"))
      (node (ref "J1") (pin "33") (pinfunction "33_33") (pintype "input"))
      (node (ref "J3") (pin "29") (pinfunction "29_29") (pintype "input"))
      (node (ref "J5") (pin "15") (pinfunction "15_15") (pintype "unspecified"))
      (node (ref "P1") (pin "29") (pinfunction "29_29") (pintype "unspecified"))
      (node (ref "R2") (pin "2") (pinfunction "2_2") (pintype "unspecified"))
    )
    (net (code "32") (name "D30") (class "Default")
      (node (ref "H2") (pin "17") (pinfunction "17_17") (pintype "unspecified"))
      (node (ref "H3") (pin "30") (pinfunction "30_30") (pintype "input"))
      (node (ref "H4") (pin "30") (pinfunction "30_30") (pintype "input"))
      (node (ref "J1") (pin "34") (pinfunction "34_34") (pintype "input"))
      (node (ref "J10") (pin "15") (pinfunction "15_15") (pintype "unspecified"))
      (node (ref "J3") (pin "30") (pinfunction "30_30") (pintype "input"))
      (node (ref "P1") (pin "30") (pinfunction "30_30") (pintype "unspecified"))
    )
    (net (code "33") (name "D31") (class "Default")
      (node (ref "H1") (pin "18") (pinfunction "18_18") (pintype "unspecified"))
      (node (ref "H3") (pin "31") (pinfunction "31_31") (pintype "input"))
      (node (ref "H4") (pin "31") (pinfunction "31_31") (pintype "input"))
      (node (ref "J1") (pin "35") (pinfunction "35_35") (pintype "input"))
      (node (ref "J3") (pin "31") (pinfunction "31_31") (pintype "input"))
      (node (ref "J5") (pin "16") (pinfunction "16_16") (pintype "unspecified"))
      (node (ref "P1") (pin "31") (pinfunction "31_31") (pintype "unspecified"))
      (node (ref "R3") (pin "2") (pinfunction "2_2") (pintype "unspecified"))
    )
    (net (code "34") (name "D32") (class "Default")
      (node (ref "H2") (pin "18") (pinfunction "18_18") (pintype "unspecified"))
      (node (ref "H3") (pin "32") (pinfunction "32_32") (pintype "input"))
      (node (ref "H4") (pin "32") (pinfunction "32_32") (pintype "input"))
      (node (ref "J1") (pin "36") (pinfunction "36_36") (pintype "input"))
      (node (ref "J10") (pin "16") (pinfunction "16_16") (pintype "unspecified"))
      (node (ref "J3") (pin "32") (pinfunction "32_32") (pintype "input"))
      (node (ref "P1") (pin "32") (pinfunction "32_32") (pintype "unspecified"))
    )
    (net (code "35") (name "D33") (class "Default")
      (node (ref "H2") (pin "19") (pinfunction "19_19") (pintype "unspecified"))
      (node (ref "H3") (pin "33") (pinfunction "33_33") (pintype "input"))
      (node (ref "H4") (pin "33") (pinfunction "33_33") (pintype "input"))
      (node (ref "J1") (pin "37") (pinfunction "37_37") (pintype "input"))
      (node (ref "J3") (pin "33") (pinfunction "33_33") (pintype "input"))
      (node (ref "J5") (pin "17") (pinfunction "17_17") (pintype "unspecified"))
      (node (ref "P1") (pin "33") (pinfunction "33_33") (pintype "unspecified"))
      (node (ref "R4") (pin "2") (pinfunction "2_2") (pintype "unspecified"))
    )
    (net (code "36") (name "D34") (class "Default")
      (node (ref "H2") (pin "20") (pinfunction "20_20") (pintype "unspecified"))
      (node (ref "H3") (pin "34") (pinfunction "34_34") (pintype "input"))
      (node (ref "H4") (pin "34") (pinfunction "34_34") (pintype "input"))
      (node (ref "J1") (pin "38") (pinfunction "38_38") (pintype "input"))
      (node (ref "J10") (pin "17") (pinfunction "17_17") (pintype "unspecified"))
      (node (ref "J3") (pin "34") (pinfunction "34_34") (pintype "input"))
      (node (ref "P1") (pin "34") (pinfunction "34_34") (pintype "unspecified"))
    )
    (net (code "37") (name "D35") (class "Default")
      (node (ref "H3") (pin "35") (pinfunction "35_35") (pintype "input"))
      (node (ref "H4") (pin "35") (pinfunction "35_35") (pintype "input"))
      (node (ref "J1") (pin "39") (pinfunction "39_39") (pintype "input"))
      (node (ref "J3") (pin "35") (pinfunction "35_35") (pintype "input"))
      (node (ref "J5") (pin "18") (pinfunction "18_18") (pintype "unspecified"))
      (node (ref "KEY1") (pin "3") (pinfunction "3_3") (pintype "unspecified"))
      (node (ref "KEY1") (pin "4") (pinfunction "4_4") (pintype "unspecified"))
      (node (ref "P1") (pin "35") (pinfunction "35_35") (pintype "unspecified"))
    )
    (net (code "38") (name "D36") (class "Default")
      (node (ref "H3") (pin "36") (pinfunction "36_36") (pintype "input"))
      (node (ref "H4") (pin "36") (pinfunction "36_36") (pintype "input"))
      (node (ref "J1") (pin "40") (pinfunction "40_40") (pintype "input"))
      (node (ref "J10") (pin "18") (pinfunction "18_18") (pintype "unspecified"))
      (node (ref "J3") (pin "36") (pinfunction "36_36") (pintype "input"))
      (node (ref "KEY2") (pin "3") (pinfunction "3_3") (pintype "unspecified"))
      (node (ref "KEY2") (pin "4") (pinfunction "4_4") (pintype "unspecified"))
      (node (ref "P1") (pin "36") (pinfunction "36_36") (pintype "unspecified"))
    )
    (net (code "39") (name "GND") (class "Default")
      (node (ref "D1") (pin "2") (pinfunction "2_2") (pintype "unspecified"))
      (node (ref "D2") (pin "2") (pinfunction "2_2") (pintype "unspecified"))
      (node (ref "D3") (pin "2") (pinfunction "2_2") (pintype "unspecified"))
      (node (ref "D4") (pin "2") (pinfunction "2_2") (pintype "unspecified"))
      (node (ref "H1") (pin "20") (pinfunction "20_20") (pintype "unspecified"))
      (node (ref "H2") (pin "15") (pinfunction "15_15") (pintype "unspecified"))
      (node (ref "H2") (pin "2") (pinfunction "2_2") (pintype "unspecified"))
      (node (ref "H5") (pin "1") (pinfunction "1_1") (pintype "unspecified"))
      (node (ref "H5") (pin "2") (pinfunction "2_2") (pintype "unspecified"))
      (node (ref "H5") (pin "3") (pinfunction "3_3") (pintype "unspecified"))
      (node (ref "J1") (pin "12") (pinfunction "12_12") (pintype "input"))
      (node (ref "J1") (pin "30") (pinfunction "30_30") (pintype "input"))
      (node (ref "J13") (pin "1") (pinfunction "1_1") (pintype "unspecified"))
      (node (ref "J13") (pin "10") (pinfunction "10_10") (pintype "unspecified"))
      (node (ref "J13") (pin "11") (pinfunction "11_11") (pintype "unspecified"))
      (node (ref "J13") (pin "12") (pinfunction "12_12") (pintype "unspecified"))
      (node (ref "J13") (pin "13") (pinfunction "13_13") (pintype "unspecified"))
      (node (ref "J13") (pin "14") (pinfunction "14_14") (pintype "unspecified"))
      (node (ref "J13") (pin "15") (pinfunction "15_15") (pintype "unspecified"))
      (node (ref "J13") (pin "16") (pinfunction "16_16") (pintype "unspecified"))
      (node (ref "J13") (pin "17") (pinfunction "17_17") (pintype "unspecified"))
      (node (ref "J13") (pin "18") (pinfunction "18_18") (pintype "unspecified"))
      (node (ref "J13") (pin "19") (pinfunction "19_19") (pintype "unspecified"))
      (node (ref "J13") (pin "2") (pinfunction "2_2") (pintype "unspecified"))
      (node (ref "J13") (pin "20") (pinfunction "20_20") (pintype "unspecified"))
      (node (ref "J13") (pin "3") (pinfunction "3_3") (pintype "unspecified"))
      (node (ref "J13") (pin "4") (pinfunction "4_4") (pintype "unspecified"))
      (node (ref "J13") (pin "5") (pinfunction "5_5") (pintype "unspecified"))
      (node (ref "J13") (pin "6") (pinfunction "6_6") (pintype "unspecified"))
      (node (ref "J13") (pin "7") (pinfunction "7_7") (pintype "unspecified"))
      (node (ref "J13") (pin "8") (pinfunction "8_8") (pintype "unspecified"))
      (node (ref "J13") (pin "9") (pinfunction "9_9") (pintype "unspecified"))
      (node (ref "J4") (pin "1") (pinfunction "1_1") (pintype "unspecified"))
      (node (ref "J4") (pin "10") (pinfunction "10_10") (pintype "unspecified"))
      (node (ref "J4") (pin "11") (pinfunction "11_11") (pintype "unspecified"))
      (node (ref "J4") (pin "12") (pinfunction "12_12") (pintype "unspecified"))
      (node (ref "J4") (pin "13") (pinfunction "13_13") (pintype "unspecified"))
      (node (ref "J4") (pin "14") (pinfunction "14_14") (pintype "unspecified"))
      (node (ref "J4") (pin "15") (pinfunction "15_15") (pintype "unspecified"))
      (node (ref "J4") (pin "16") (pinfunction "16_16") (pintype "unspecified"))
      (node (ref "J4") (pin "17") (pinfunction "17_17") (pintype "unspecified"))
      (node (ref "J4") (pin "18") (pinfunction "18_18") (pintype "unspecified"))
      (node (ref "J4") (pin "19") (pinfunction "19_19") (pintype "unspecified"))
      (node (ref "J4") (pin "2") (pinfunction "2_2") (pintype "unspecified"))
      (node (ref "J4") (pin "20") (pinfunction "20_20") (pintype "unspecified"))
      (node (ref "J4") (pin "3") (pinfunction "3_3") (pintype "unspecified"))
      (node (ref "J4") (pin "4") (pinfunction "4_4") (pintype "unspecified"))
      (node (ref "J4") (pin "5") (pinfunction "5_5") (pintype "unspecified"))
      (node (ref "J4") (pin "6") (pinfunction "6_6") (pintype "unspecified"))
      (node (ref "J4") (pin "7") (pinfunction "7_7") (pintype "unspecified"))
      (node (ref "J4") (pin "8") (pinfunction "8_8") (pintype "unspecified"))
      (node (ref "J4") (pin "9") (pinfunction "9_9") (pintype "unspecified"))
      (node (ref "J9") (pin "1") (pinfunction "1_1") (pintype "unspecified"))
      (node (ref "J9") (pin "2") (pinfunction "2_2") (pintype "unspecified"))
      (node (ref "J9") (pin "3") (pinfunction "3_3") (pintype "unspecified"))
      (node (ref "KEY1") (pin "1") (pinfunction "1_1") (pintype "unspecified"))
      (node (ref "KEY1") (pin "2") (pinfunction "2_2") (pintype "unspecified"))
      (node (ref "KEY2") (pin "1") (pinfunction "1_1") (pintype "unspecified"))
      (node (ref "KEY2") (pin "2") (pinfunction "2_2") (pintype "unspecified"))
    )
    (net (code "40") (name "Net-(D1-Pad1)") (class "Default")
      (node (ref "D1") (pin "1") (pinfunction "1_1") (pintype "unspecified"))
      (node (ref "R1") (pin "1") (pinfunction "1_1") (pintype "unspecified"))
    )
    (net (code "41") (name "Net-(D2-Pad1)") (class "Default")
      (node (ref "D2") (pin "1") (pinfunction "1_1") (pintype "unspecified"))
      (node (ref "R2") (pin "1") (pinfunction "1_1") (pintype "unspecified"))
    )
    (net (code "42") (name "Net-(D3-Pad1)") (class "Default")
      (node (ref "D3") (pin "1") (pinfunction "1_1") (pintype "unspecified"))
      (node (ref "R3") (pin "1") (pinfunction "1_1") (pintype "unspecified"))
    )
    (net (code "43") (name "Net-(D4-Pad1)") (class "Default")
      (node (ref "D4") (pin "1") (pinfunction "1_1") (pintype "unspecified"))
      (node (ref "R4") (pin "1") (pinfunction "1_1") (pintype "unspecified"))
    )
    (net (code "44") (name "X1") (class "Default")
      (node (ref "H3") (pin "37") (pinfunction "37_37") (pintype "input"))
      (node (ref "H4") (pin "37") (pinfunction "37_37") (pintype "input"))
      (node (ref "J3") (pin "37") (pinfunction "37_37") (pintype "input"))
      (node (ref "J5") (pin "19") (pinfunction "19_19") (pintype "unspecified"))
      (node (ref "J6") (pin "2") (pinfunction "2_2") (pintype "unspecified"))
      (node (ref "P1") (pin "37") (pinfunction "37_37") (pintype "unspecified"))
    )
    (net (code "45") (name "X2") (class "Default")
      (node (ref "H3") (pin "38") (pinfunction "38_38") (pintype "input"))
      (node (ref "H4") (pin "38") (pinfunction "38_38") (pintype "input"))
      (node (ref "J10") (pin "19") (pinfunction "19_19") (pintype "unspecified"))
      (node (ref "J3") (pin "38") (pinfunction "38_38") (pintype "input"))
      (node (ref "J6") (pin "4") (pinfunction "4_4") (pintype "unspecified"))
      (node (ref "P1") (pin "38") (pinfunction "38_38") (pintype "unspecified"))
    )
    (net (code "46") (name "X3") (class "Default")
      (node (ref "H3") (pin "39") (pinfunction "39_39") (pintype "input"))
      (node (ref "H4") (pin "39") (pinfunction "39_39") (pintype "input"))
      (node (ref "J3") (pin "39") (pinfunction "39_39") (pintype "input"))
      (node (ref "J5") (pin "20") (pinfunction "20_20") (pintype "unspecified"))
      (node (ref "J6") (pin "6") (pinfunction "6_6") (pintype "unspecified"))
      (node (ref "P1") (pin "39") (pinfunction "39_39") (pintype "unspecified"))
    )
    (net (code "47") (name "X4") (class "Default")
      (node (ref "H3") (pin "40") (pinfunction "40_40") (pintype "input"))
      (node (ref "H4") (pin "40") (pinfunction "40_40") (pintype "input"))
      (node (ref "J10") (pin "20") (pinfunction "20_20") (pintype "unspecified"))
      (node (ref "J3") (pin "40") (pinfunction "40_40") (pintype "input"))
      (node (ref "J6") (pin "8") (pinfunction "8_8") (pintype "unspecified"))
      (node (ref "P1") (pin "40") (pinfunction "40_40") (pintype "unspecified"))
    )
    (net (code "48") (name "unconnected-(P1-Pad41)") (class "Default")
      (node (ref "P1") (pin "41") (pinfunction "41_41") (pintype "unspecified"))
    )
    (net (code "49") (name "unconnected-(P1-Pad42)") (class "Default")
      (node (ref "P1") (pin "42") (pinfunction "42_42") (pintype "unspecified"))
    )
  )
)
